# metiumacs4.net
KiCad netlist of a schematic drawn in EAGLE
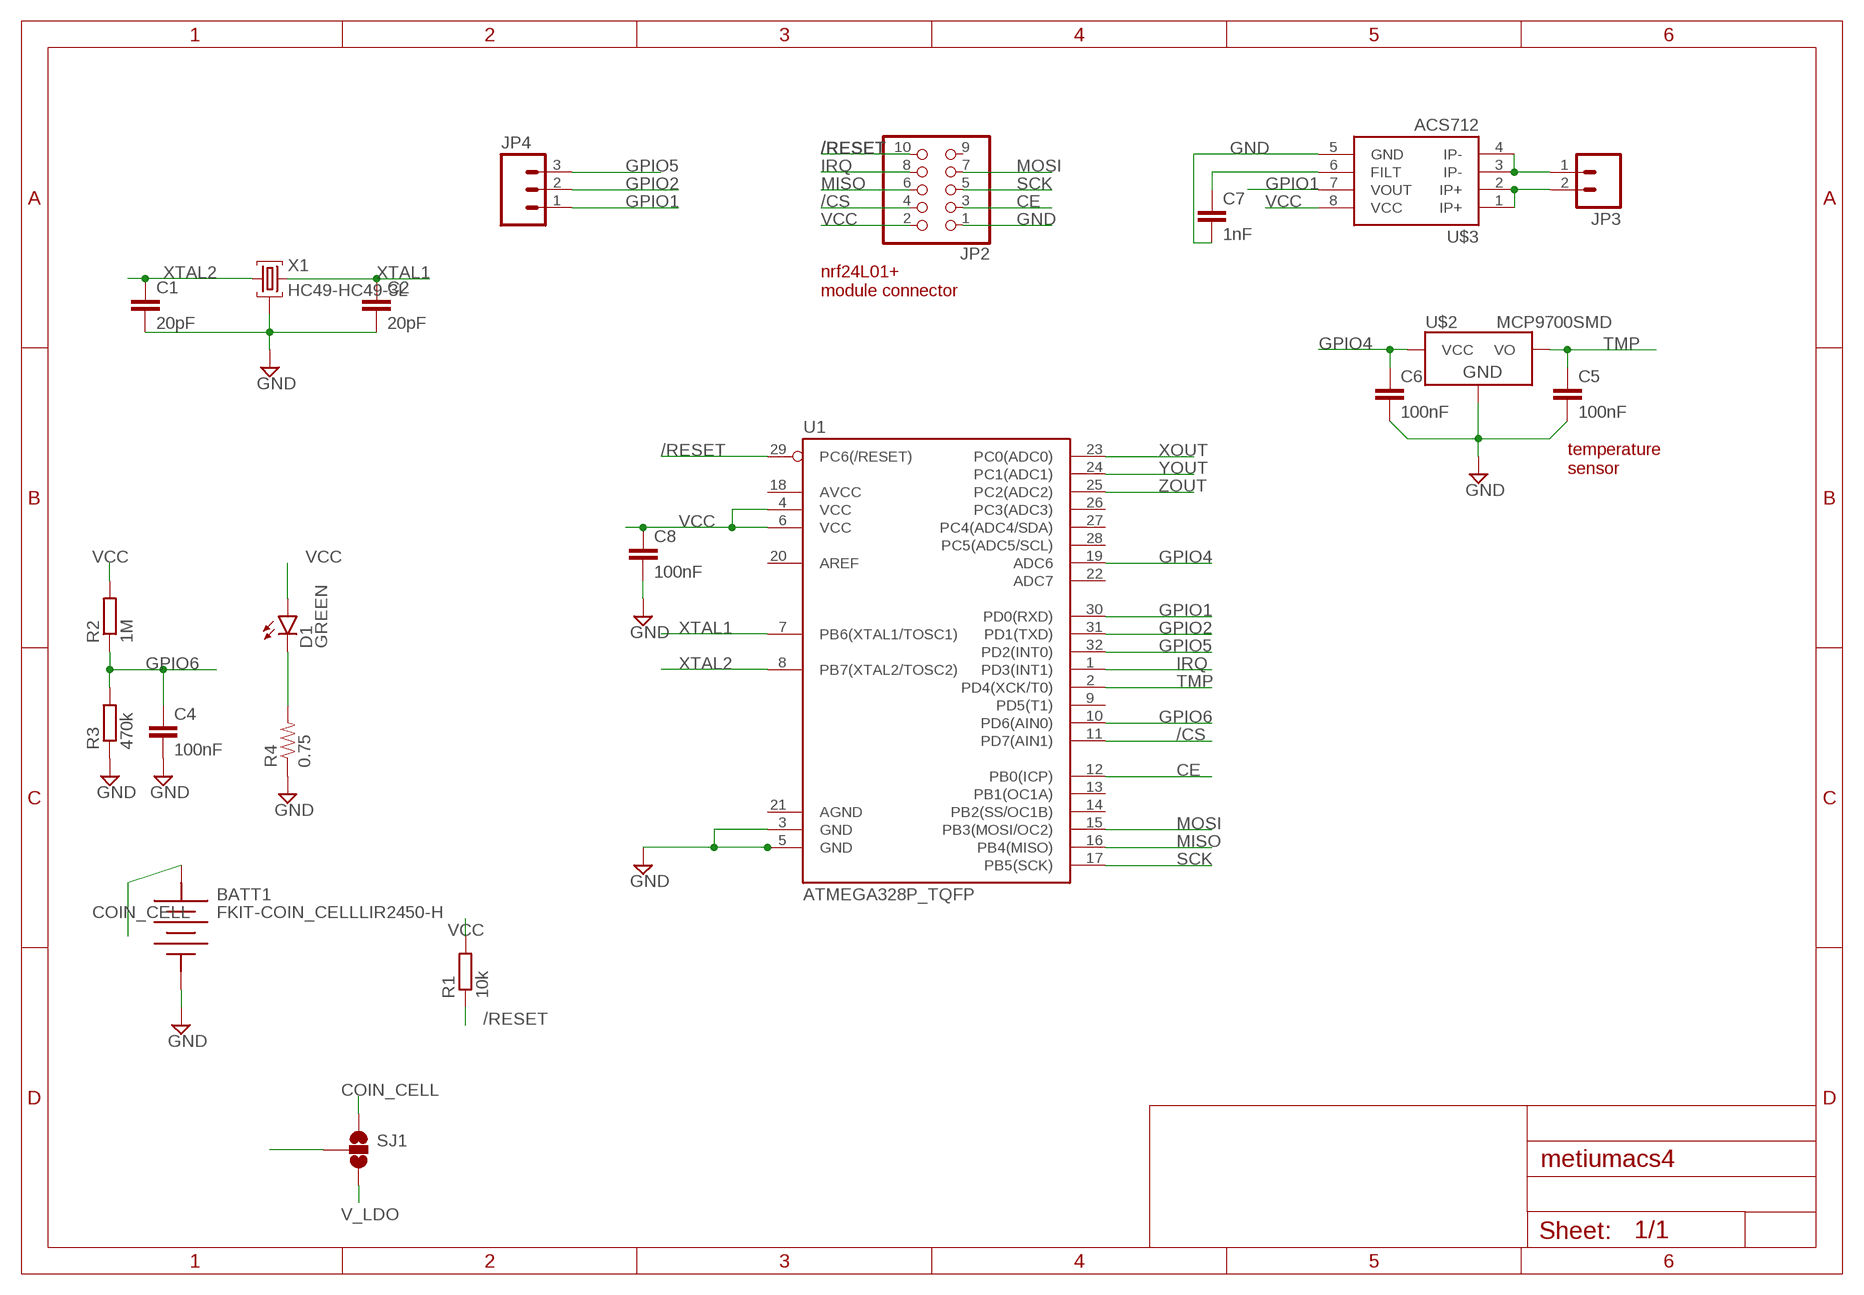
[diagram p0: schematic, sheet 1]

(export (version "E")
  (design (tool "Eeschema 10.0.6"))
  (components
    (comp (ref "BATT1")
      (value "FKIT-COIN_CELLLIR2450-H")
      (footprint "eagle-import:FKIT-LIR2450-H")
      (libsource (lib "eagle-import") (part "FKIT-COIN_CELLLIR2450-H"))
    )
    (comp (ref "C1")
      (value "20pF")
      (footprint "eagle-import:0805")
      (libsource (lib "eagle-import") (part "CAP0805"))
    )
    (comp (ref "C2")
      (value "20pF")
      (footprint "eagle-import:0805")
      (libsource (lib "eagle-import") (part "CAP0805"))
    )
    (comp (ref "C4")
      (value "100nF")
      (footprint "eagle-import:C0805")
      (libsource (lib "eagle-import") (part "C-EUC0805"))
    )
    (comp (ref "C5")
      (value "100nF")
      (footprint "eagle-import:C0805")
      (libsource (lib "eagle-import") (part "C-EUC0805"))
    )
    (comp (ref "C6")
      (value "100nF")
      (footprint "eagle-import:C0805")
      (libsource (lib "eagle-import") (part "C-EUC0805"))
    )
    (comp (ref "C7")
      (value "1nF")
      (footprint "eagle-import:0603-CAP")
      (libsource (lib "eagle-import") (part "1NF/1000PF-50V-10%(0603)"))
    )
    (comp (ref "C8")
      (value "100nF")
      (footprint "eagle-import:0805")
      (libsource (lib "eagle-import") (part "CAP0805"))
    )
    (comp (ref "D1")
      (value "GREEN")
      (footprint "eagle-import:LED-0603")
      (libsource (lib "eagle-import") (part "LED-GREEN0603"))
    )
    (comp (ref "JP2")
      (value "PINHD-2X5")
      (footprint "eagle-import:2X05M")
      (libsource (lib "eagle-import") (part "PINHD-2X5"))
    )
    (comp (ref "JP3")
      (value "M02PTH4")
      (footprint "eagle-import:1X02_XTRA_BIG")
      (libsource (lib "eagle-import") (part "M02PTH4"))
    )
    (comp (ref "JP4")
      (value "M03LONGPADS")
      (footprint "eagle-import:1X03_LONGPADS")
      (libsource (lib "eagle-import") (part "M03LONGPADS"))
    )
    (comp (ref "R1")
      (value "10k")
      (footprint "eagle-import:R0805")
      (libsource (lib "eagle-import") (part "R-EU_R0805"))
    )
    (comp (ref "R2")
      (value "1M")
      (footprint "eagle-import:R0805")
      (libsource (lib "eagle-import") (part "R-EU_R0805"))
    )
    (comp (ref "R3")
      (value "470k")
      (footprint "eagle-import:R0805")
      (libsource (lib "eagle-import") (part "R-EU_R0805"))
    )
    (comp (ref "R4")
      (value "0.75")
      (footprint "eagle-import:0805")
      (libsource (lib "eagle-import") (part "0.75OHM-1/4W-1%(0805)"))
    )
    (comp (ref "SJ1")
      (value "SOLDERJUMPER_2WAYS")
      (footprint "eagle-import:SJ_3")
      (libsource (lib "eagle-import") (part "SOLDERJUMPER_2WAYS"))
    )
    (comp (ref "U$2")
      (value "MCP9700SMD")
      (footprint "eagle-import:SOT23-3")
      (libsource (lib "eagle-import") (part "MCP9700SMD"))
    )
    (comp (ref "U$3")
      (value "ACS712")
      (footprint "eagle-import:SO08")
      (libsource (lib "eagle-import") (part "ACS712"))
    )
    (comp (ref "U1")
      (value "ATMEGA328P_TQFP")
      (footprint "eagle-import:TQFP32-08")
      (libsource (lib "eagle-import") (part "ATMEGA328P_TQFP"))
    )
    (comp (ref "X1")
      (value "HC49-HC49-3L")
      (footprint "eagle-import:HC49-3L")
      (libsource (lib "eagle-import") (part "HC49-HC49-3L"))
    )
  )
  (nets
    (net (code "1") (name "/CE") (class "Default")
      (node (ref "JP2") (pin "3") (pinfunction "3_3") (pintype "passive"))
      (node (ref "U1") (pin "12") (pinfunction "PB0(ICP)_12") (pintype "bidirectional"))
    )
    (net (code "2") (name "/COIN_CELL") (class "Default")
      (node (ref "BATT1") (pin "POS") (pinfunction "POS_POS") (pintype "bidirectional"))
      (node (ref "SJ1") (pin "1") (pinfunction "1_1") (pintype "passive"))
    )
    (net (code "3") (name "/GPIO1") (class "Default")
      (node (ref "JP4") (pin "1") (pinfunction "1_1") (pintype "passive"))
      (node (ref "U$3") (pin "7") (pinfunction "VOUT_7") (pintype "bidirectional"))
      (node (ref "U1") (pin "30") (pinfunction "PD0(RXD)_30") (pintype "bidirectional"))
    )
    (net (code "4") (name "/GPIO2") (class "Default")
      (node (ref "JP4") (pin "2") (pinfunction "2_2") (pintype "passive"))
      (node (ref "U1") (pin "31") (pinfunction "PD1(TXD)_31") (pintype "bidirectional"))
    )
    (net (code "5") (name "/GPIO4") (class "Default")
      (node (ref "C6") (pin "1") (pinfunction "1_1") (pintype "passive"))
      (node (ref "U$2") (pin "1") (pinfunction "VCC_1") (pintype "bidirectional"))
      (node (ref "U1") (pin "19") (pinfunction "ADC6_19") (pintype "bidirectional"))
    )
    (net (code "6") (name "/GPIO5") (class "Default")
      (node (ref "JP4") (pin "3") (pinfunction "3_3") (pintype "passive"))
      (node (ref "U1") (pin "32") (pinfunction "PD2(INT0)_32") (pintype "bidirectional"))
    )
    (net (code "7") (name "/GPIO6") (class "Default")
      (node (ref "C4") (pin "1") (pinfunction "1_1") (pintype "passive"))
      (node (ref "R2") (pin "1") (pinfunction "1_1") (pintype "passive"))
      (node (ref "R3") (pin "2") (pinfunction "2_2") (pintype "passive"))
      (node (ref "U1") (pin "10") (pinfunction "PD6(AIN0)_10") (pintype "bidirectional"))
    )
    (net (code "8") (name "/IRQ") (class "Default")
      (node (ref "JP2") (pin "8") (pinfunction "8_8") (pintype "passive"))
      (node (ref "U1") (pin "1") (pinfunction "PD3(INT1)_1") (pintype "bidirectional"))
    )
    (net (code "9") (name "/MISO") (class "Default")
      (node (ref "JP2") (pin "6") (pinfunction "6_6") (pintype "passive"))
      (node (ref "U1") (pin "16") (pinfunction "PB4(MISO)_16") (pintype "bidirectional"))
    )
    (net (code "10") (name "/MOSI") (class "Default")
      (node (ref "JP2") (pin "7") (pinfunction "7_7") (pintype "passive"))
      (node (ref "U1") (pin "15") (pinfunction "PB3(MOSI/OC2)_15") (pintype "bidirectional"))
    )
    (net (code "11") (name "/SCK") (class "Default")
      (node (ref "JP2") (pin "5") (pinfunction "5_5") (pintype "passive"))
      (node (ref "U1") (pin "17") (pinfunction "PB5(SCK)_17") (pintype "bidirectional"))
    )
    (net (code "12") (name "/TMP") (class "Default")
      (node (ref "C5") (pin "1") (pinfunction "1_1") (pintype "passive"))
      (node (ref "U$2") (pin "2") (pinfunction "VO_2") (pintype "bidirectional"))
      (node (ref "U1") (pin "2") (pinfunction "PD4(XCK/T0)_2") (pintype "bidirectional"))
    )
    (net (code "13") (name "/VCC") (class "Default")
      (node (ref "C8") (pin "1") (pinfunction "1_1") (pintype "passive"))
      (node (ref "D1") (pin "A") (pinfunction "A_A") (pintype "passive"))
      (node (ref "JP2") (pin "2") (pinfunction "2_2") (pintype "passive"))
      (node (ref "R1") (pin "2") (pinfunction "2_2") (pintype "passive"))
      (node (ref "R2") (pin "2") (pinfunction "2_2") (pintype "passive"))
      (node (ref "SJ1") (pin "2") (pinfunction "2_2") (pintype "passive"))
      (node (ref "U$3") (pin "8") (pinfunction "VCC_8") (pintype "bidirectional"))
      (node (ref "U1") (pin "4") (pinfunction "VCC_4") (pintype "bidirectional"))
      (node (ref "U1") (pin "6") (pinfunction "VCC_6") (pintype "bidirectional"))
    )
    (net (code "14") (name "/V_LDO") (class "Default")
      (node (ref "SJ1") (pin "3") (pinfunction "3_3") (pintype "passive"))
    )
    (net (code "15") (name "/XOUT") (class "Default")
      (node (ref "U1") (pin "23") (pinfunction "PC0(ADC0)_23") (pintype "bidirectional"))
    )
    (net (code "16") (name "/XTAL1") (class "Default")
      (node (ref "C2") (pin "1") (pinfunction "1_1") (pintype "passive"))
      (node (ref "U1") (pin "7") (pinfunction "PB6(XTAL1/TOSC1)_7") (pintype "bidirectional"))
      (node (ref "X1") (pin "3") (pinfunction "3_3") (pintype "passive"))
    )
    (net (code "17") (name "/XTAL2") (class "Default")
      (node (ref "C1") (pin "1") (pinfunction "1_1") (pintype "passive"))
      (node (ref "U1") (pin "8") (pinfunction "PB7(XTAL2/TOSC2)_8") (pintype "bidirectional"))
      (node (ref "X1") (pin "1") (pinfunction "1_1") (pintype "passive"))
    )
    (net (code "18") (name "/YOUT") (class "Default")
      (node (ref "U1") (pin "24") (pinfunction "PC1(ADC1)_24") (pintype "bidirectional"))
    )
    (net (code "19") (name "/ZOUT") (class "Default")
      (node (ref "U1") (pin "25") (pinfunction "PC2(ADC2)_25") (pintype "bidirectional"))
    )
    (net (code "20") (name "/{slash}CS") (class "Default")
      (node (ref "JP2") (pin "4") (pinfunction "4_4") (pintype "passive"))
      (node (ref "U1") (pin "11") (pinfunction "PD7(AIN1)_11") (pintype "bidirectional"))
    )
    (net (code "21") (name "/{slash}RESET") (class "Default")
      (node (ref "JP2") (pin "10") (pinfunction "10_10") (pintype "passive"))
      (node (ref "R1") (pin "1") (pinfunction "1_1") (pintype "passive"))
      (node (ref "U1") (pin "29") (pinfunction "PC6(/RESET)_29") (pintype "bidirectional"))
    )
    (net (code "22") (name "GND") (class "Default")
      (node (ref "BATT1") (pin "NEG") (pinfunction "NEG_NEG") (pintype "bidirectional"))
      (node (ref "C1") (pin "2") (pinfunction "2_2") (pintype "passive"))
      (node (ref "C2") (pin "2") (pinfunction "2_2") (pintype "passive"))
      (node (ref "C4") (pin "2") (pinfunction "2_2") (pintype "passive"))
      (node (ref "C5") (pin "2") (pinfunction "2_2") (pintype "passive"))
      (node (ref "C6") (pin "2") (pinfunction "2_2") (pintype "passive"))
      (node (ref "C7") (pin "2") (pinfunction "2_2") (pintype "passive"))
      (node (ref "C8") (pin "2") (pinfunction "2_2") (pintype "passive"))
      (node (ref "JP2") (pin "1") (pinfunction "1_1") (pintype "passive"))
      (node (ref "R3") (pin "1") (pinfunction "1_1") (pintype "passive"))
      (node (ref "R4") (pin "1") (pinfunction "1_1") (pintype "passive"))
      (node (ref "U$2") (pin "3") (pinfunction "GND_3") (pintype "bidirectional"))
      (node (ref "U$3") (pin "5") (pinfunction "GND_5") (pintype "bidirectional"))
      (node (ref "U1") (pin "3") (pinfunction "GND_3") (pintype "bidirectional"))
      (node (ref "U1") (pin "5") (pinfunction "GND_5") (pintype "bidirectional"))
      (node (ref "X1") (pin "2") (pinfunction "2_2") (pintype "passive"))
    )
    (net (code "23") (name "Net-(D1-PadC)") (class "Default")
      (node (ref "D1") (pin "C") (pinfunction "C_C") (pintype "passive"))
      (node (ref "R4") (pin "2") (pinfunction "2_2") (pintype "passive"))
    )
    (net (code "24") (name "Net-(JP3-Pad1)") (class "Default")
      (node (ref "JP3") (pin "1") (pinfunction "1_1") (pintype "passive"))
      (node (ref "U$3") (pin "3") (pinfunction "IP-_3") (pintype "bidirectional"))
      (node (ref "U$3") (pin "4") (pinfunction "IP-_4") (pintype "bidirectional"))
    )
    (net (code "25") (name "Net-(JP3-Pad2)") (class "Default")
      (node (ref "JP3") (pin "2") (pinfunction "2_2") (pintype "passive"))
      (node (ref "U$3") (pin "1") (pinfunction "IP+_1") (pintype "bidirectional"))
      (node (ref "U$3") (pin "2") (pinfunction "IP+_2") (pintype "bidirectional"))
    )
    (net (code "26") (name "Net-(U$3-FILT)") (class "Default")
      (node (ref "C7") (pin "1") (pinfunction "1_1") (pintype "passive"))
      (node (ref "U$3") (pin "6") (pinfunction "FILT_6") (pintype "bidirectional"))
    )
    (net (code "27") (name "unconnected-(JP2-Pad9)") (class "Default")
      (node (ref "JP2") (pin "9") (pinfunction "9_9") (pintype "passive"))
    )
    (net (code "28") (name "unconnected-(U1-ADC7-Pad22)") (class "Default")
      (node (ref "U1") (pin "22") (pinfunction "ADC7_22") (pintype "bidirectional"))
    )
    (net (code "29") (name "unconnected-(U1-AGND-Pad21)") (class "Default")
      (node (ref "U1") (pin "21") (pinfunction "AGND_21") (pintype "bidirectional"))
    )
    (net (code "30") (name "unconnected-(U1-AREF-Pad20)") (class "Default")
      (node (ref "U1") (pin "20") (pinfunction "AREF_20") (pintype "bidirectional"))
    )
    (net (code "31") (name "unconnected-(U1-AVCC-Pad18)") (class "Default")
      (node (ref "U1") (pin "18") (pinfunction "AVCC_18") (pintype "bidirectional"))
    )
    (net (code "32") (name "unconnected-(U1-PB1(OC1A)-Pad13)") (class "Default")
      (node (ref "U1") (pin "13") (pinfunction "PB1(OC1A)_13") (pintype "bidirectional"))
    )
    (net (code "33") (name "unconnected-(U1-PB2(SS{slash}OC1B)-Pad14)") (class "Default")
      (node (ref "U1") (pin "14") (pinfunction "PB2(SS/OC1B)_14") (pintype "bidirectional"))
    )
    (net (code "34") (name "unconnected-(U1-PC3(ADC3)-Pad26)") (class "Default")
      (node (ref "U1") (pin "26") (pinfunction "PC3(ADC3)_26") (pintype "bidirectional"))
    )
    (net (code "35") (name "unconnected-(U1-PC4(ADC4{slash}SDA)-Pad27)") (class "Default")
      (node (ref "U1") (pin "27") (pinfunction "PC4(ADC4/SDA)_27") (pintype "bidirectional"))
    )
    (net (code "36") (name "unconnected-(U1-PC5(ADC5{slash}SCL)-Pad28)") (class "Default")
      (node (ref "U1") (pin "28") (pinfunction "PC5(ADC5/SCL)_28") (pintype "bidirectional"))
    )
    (net (code "37") (name "unconnected-(U1-PD5(T1)-Pad9)") (class "Default")
      (node (ref "U1") (pin "9") (pinfunction "PD5(T1)_9") (pintype "bidirectional"))
    )
  )
)
